# netCPU.net
KiCad netlist of a schematic drawn in EAGLE
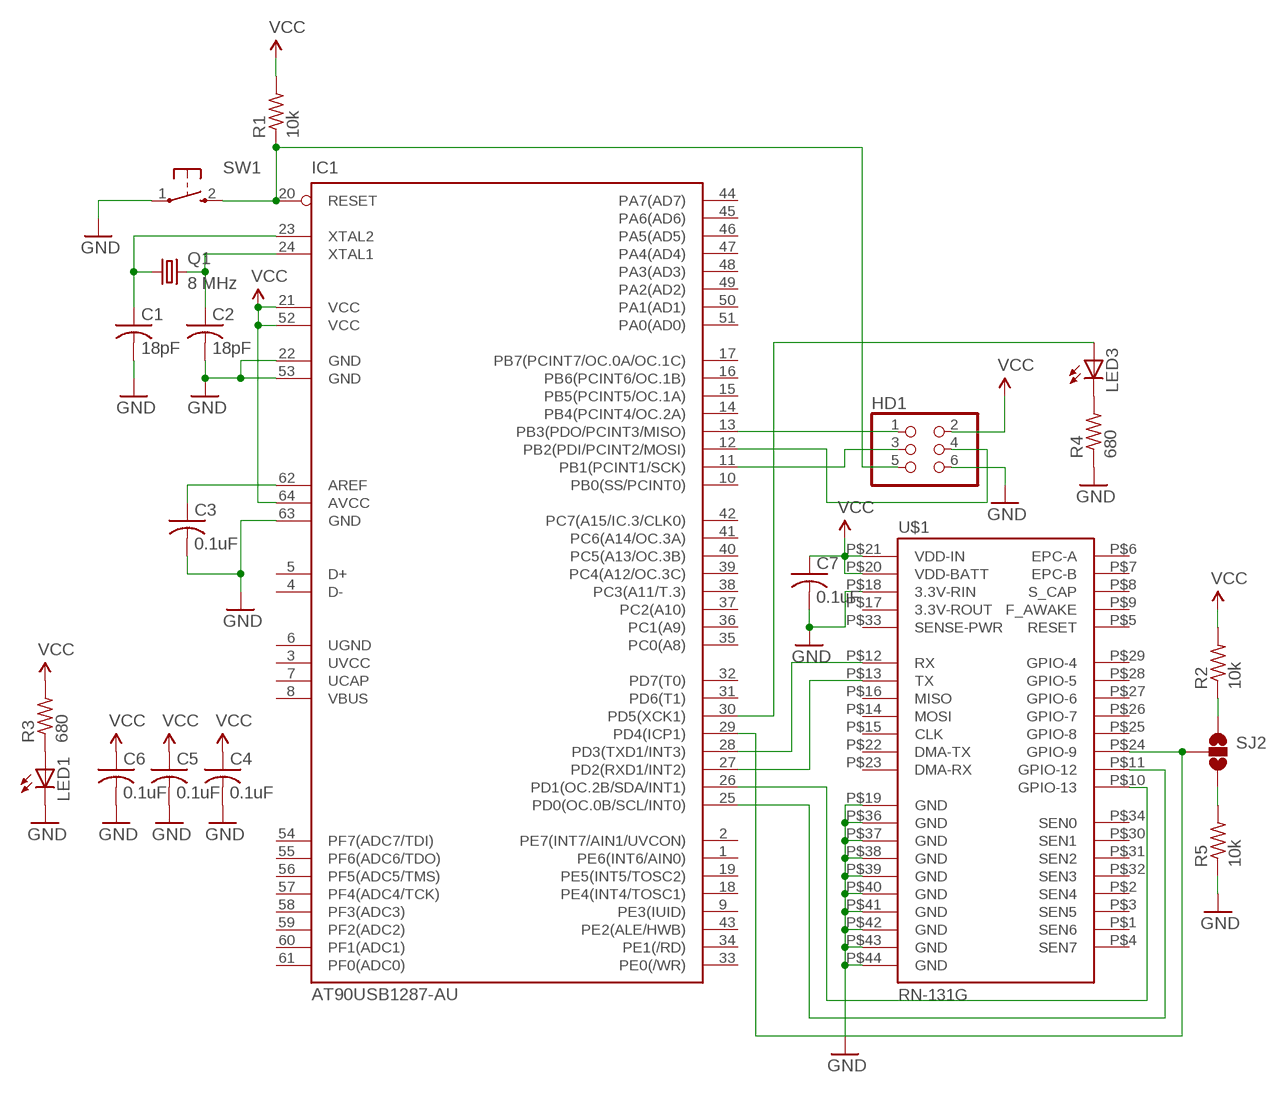
[diagram p0: schematic, sheet 1]

(export (version "E")
  (design (tool "Eeschema 10.0.6"))
  (components
    (comp (ref "C1")
      (value "18pF")
      (footprint "eagle-import:C0603K")
      (libsource (lib "eagle-import") (part "C-USC0603K"))
    )
    (comp (ref "C2")
      (value "18pF")
      (footprint "eagle-import:C0603K")
      (libsource (lib "eagle-import") (part "C-USC0603K"))
    )
    (comp (ref "C3")
      (value "0.1uF")
      (footprint "eagle-import:C0603K")
      (libsource (lib "eagle-import") (part "C-USC0603K"))
    )
    (comp (ref "C4")
      (value "0.1uF")
      (footprint "eagle-import:C0603K")
      (libsource (lib "eagle-import") (part "C-USC0603K"))
    )
    (comp (ref "C5")
      (value "0.1uF")
      (footprint "eagle-import:C0603K")
      (libsource (lib "eagle-import") (part "C-USC0603K"))
    )
    (comp (ref "C6")
      (value "0.1uF")
      (footprint "eagle-import:C0603K")
      (libsource (lib "eagle-import") (part "C-USC0603K"))
    )
    (comp (ref "C7")
      (value "0.1uF")
      (footprint "eagle-import:C0603K")
      (libsource (lib "eagle-import") (part "C-USC0603K"))
    )
    (comp (ref "HD1")
      (value "HEADER2X3")
      (footprint "eagle-import:HEADER2X3")
      (libsource (lib "eagle-import") (part "HEADER2X3"))
    )
    (comp (ref "IC1")
      (value "AT90USB1287-AU")
      (footprint "eagle-import:TQFP64")
      (libsource (lib "eagle-import") (part "AT90USB1287-AU"))
    )
    (comp (ref "LED1")
      (value "LEDCHIP-LED0603")
      (footprint "eagle-import:CHIP-LED0603")
      (libsource (lib "eagle-import") (part "LEDCHIP-LED0603"))
    )
    (comp (ref "LED3")
      (value "LEDCHIP-LED0603")
      (footprint "eagle-import:CHIP-LED0603")
      (libsource (lib "eagle-import") (part "LEDCHIP-LED0603"))
    )
    (comp (ref "Q1")
      (value "8 MHz")
      (footprint "eagle-import:HC49UP")
      (libsource (lib "eagle-import") (part "CRYSTALHC49UP"))
    )
    (comp (ref "R1")
      (value "10k")
      (footprint "eagle-import:R0603")
      (libsource (lib "eagle-import") (part "R-US_R0603"))
    )
    (comp (ref "R2")
      (value "10k")
      (footprint "eagle-import:R0603")
      (libsource (lib "eagle-import") (part "R-US_R0603"))
    )
    (comp (ref "R3")
      (value "680")
      (footprint "eagle-import:R0603")
      (libsource (lib "eagle-import") (part "R-US_R0603"))
    )
    (comp (ref "R4")
      (value "680")
      (footprint "eagle-import:R0603")
      (libsource (lib "eagle-import") (part "R-US_R0603"))
    )
    (comp (ref "R5")
      (value "10k")
      (footprint "eagle-import:R0603")
      (libsource (lib "eagle-import") (part "R-US_R0603"))
    )
    (comp (ref "SJ2")
      (value "SOLDERJUMPER_2WAYPASTE2&3")
      (footprint "eagle-import:SJ_3_PASTE2&3")
      (libsource (lib "eagle-import") (part "SOLDERJUMPER_2WAYPASTE2&3"))
    )
    (comp (ref "SW1")
      (value "TAC-SWITCH")
      (footprint "eagle-import:TAC-SWITCH")
      (libsource (lib "eagle-import") (part "TAC-SWITCH"))
    )
    (comp (ref "U$1")
      (value "RN-131G")
      (footprint "eagle-import:RN-131G")
      (libsource (lib "eagle-import") (part "RN-131G"))
    )
  )
  (nets
    (net (code "1") (name "/UCAP") (class "Default")
      (node (ref "IC1") (pin "7") (pinfunction "UCAP_7") (pintype "power_in"))
    )
    (net (code "2") (name "/UGND") (class "Default")
      (node (ref "IC1") (pin "6") (pinfunction "UGND_6") (pintype "power_in"))
    )
    (net (code "3") (name "/UVCC") (class "Default")
      (node (ref "IC1") (pin "3") (pinfunction "UVCC_3") (pintype "power_in"))
    )
    (net (code "4") (name "/VBUS") (class "Default")
      (node (ref "IC1") (pin "8") (pinfunction "VBUS_8") (pintype "power_in"))
    )
    (net (code "5") (name "GND") (class "Default")
      (node (ref "C1") (pin "2") (pinfunction "2_2") (pintype "passive"))
      (node (ref "C2") (pin "2") (pinfunction "2_2") (pintype "passive"))
      (node (ref "C3") (pin "2") (pinfunction "2_2") (pintype "passive"))
      (node (ref "C4") (pin "2") (pinfunction "2_2") (pintype "passive"))
      (node (ref "C5") (pin "2") (pinfunction "2_2") (pintype "passive"))
      (node (ref "C6") (pin "2") (pinfunction "2_2") (pintype "passive"))
      (node (ref "C7") (pin "2") (pinfunction "2_2") (pintype "passive"))
      (node (ref "HD1") (pin "6") (pinfunction "6_6") (pintype "passive"))
      (node (ref "IC1") (pin "22") (pinfunction "GND_22") (pintype "power_in"))
      (node (ref "IC1") (pin "53") (pinfunction "GND_53") (pintype "power_in"))
      (node (ref "IC1") (pin "63") (pinfunction "GND_63") (pintype "power_in"))
      (node (ref "LED1") (pin "C") (pinfunction "C_C") (pintype "passive"))
      (node (ref "R4") (pin "1") (pinfunction "1_1") (pintype "passive"))
      (node (ref "R5") (pin "1") (pinfunction "1_1") (pintype "passive"))
      (node (ref "SW1") (pin "1") (pinfunction "1_1") (pintype "passive"))
      (node (ref "U$1") (pin "P$18") (pinfunction "3.3V-RIN_P$18") (pintype "bidirectional"))
      (node (ref "U$1") (pin "P$19") (pinfunction "GND_P$19") (pintype "bidirectional"))
      (node (ref "U$1") (pin "P$36") (pinfunction "GND_P$36") (pintype "bidirectional"))
      (node (ref "U$1") (pin "P$37") (pinfunction "GND_P$37") (pintype "bidirectional"))
      (node (ref "U$1") (pin "P$38") (pinfunction "GND_P$38") (pintype "bidirectional"))
      (node (ref "U$1") (pin "P$39") (pinfunction "GND_P$39") (pintype "bidirectional"))
      (node (ref "U$1") (pin "P$40") (pinfunction "GND_P$40") (pintype "bidirectional"))
      (node (ref "U$1") (pin "P$41") (pinfunction "GND_P$41") (pintype "bidirectional"))
      (node (ref "U$1") (pin "P$42") (pinfunction "GND_P$42") (pintype "bidirectional"))
      (node (ref "U$1") (pin "P$43") (pinfunction "GND_P$43") (pintype "bidirectional"))
      (node (ref "U$1") (pin "P$44") (pinfunction "GND_P$44") (pintype "bidirectional"))
    )
    (net (code "6") (name "Net-(IC1-AREF)") (class "Default")
      (node (ref "C3") (pin "1") (pinfunction "1_1") (pintype "passive"))
      (node (ref "IC1") (pin "62") (pinfunction "AREF_62") (pintype "bidirectional"))
    )
    (net (code "7") (name "Net-(IC1-PB1(PCINT1{slash}SCK))") (class "Default")
      (node (ref "HD1") (pin "3") (pinfunction "3_3") (pintype "passive"))
      (node (ref "IC1") (pin "11") (pinfunction "PB1(PCINT1/SCK)_11") (pintype "bidirectional"))
    )
    (net (code "8") (name "Net-(IC1-PB2(PDI{slash}PCINT2{slash}MOSI))") (class "Default")
      (node (ref "HD1") (pin "4") (pinfunction "4_4") (pintype "passive"))
      (node (ref "IC1") (pin "12") (pinfunction "PB2(PDI/PCINT2/MOSI)_12") (pintype "bidirectional"))
    )
    (net (code "9") (name "Net-(IC1-PB3(PDO{slash}PCINT3{slash}MISO))") (class "Default")
      (node (ref "HD1") (pin "1") (pinfunction "1_1") (pintype "passive"))
      (node (ref "IC1") (pin "13") (pinfunction "PB3(PDO/PCINT3/MISO)_13") (pintype "bidirectional"))
    )
    (net (code "10") (name "Net-(IC1-PD0(OC.0B{slash}SCL{slash}INT0))") (class "Default")
      (node (ref "IC1") (pin "25") (pinfunction "PD0(OC.0B/SCL/INT0)_25") (pintype "bidirectional"))
      (node (ref "U$1") (pin "P$11") (pinfunction "GPIO-12_P$11") (pintype "bidirectional"))
    )
    (net (code "11") (name "Net-(IC1-PD1(OC.2B{slash}SDA{slash}INT1))") (class "Default")
      (node (ref "IC1") (pin "26") (pinfunction "PD1(OC.2B/SDA/INT1)_26") (pintype "bidirectional"))
      (node (ref "U$1") (pin "P$10") (pinfunction "GPIO-13_P$10") (pintype "bidirectional"))
    )
    (net (code "12") (name "Net-(IC1-PD2(RXD1{slash}INT2))") (class "Default")
      (node (ref "IC1") (pin "27") (pinfunction "PD2(RXD1/INT2)_27") (pintype "bidirectional"))
      (node (ref "U$1") (pin "P$13") (pinfunction "TX_P$13") (pintype "bidirectional"))
    )
    (net (code "13") (name "Net-(IC1-PD3(TXD1{slash}INT3))") (class "Default")
      (node (ref "IC1") (pin "28") (pinfunction "PD3(TXD1/INT3)_28") (pintype "bidirectional"))
      (node (ref "U$1") (pin "P$12") (pinfunction "RX_P$12") (pintype "bidirectional"))
    )
    (net (code "14") (name "Net-(IC1-PD4(ICP1))") (class "Default")
      (node (ref "IC1") (pin "29") (pinfunction "PD4(ICP1)_29") (pintype "bidirectional"))
      (node (ref "SJ2") (pin "2") (pinfunction "2_2") (pintype "passive"))
      (node (ref "U$1") (pin "P$24") (pinfunction "GPIO-9_P$24") (pintype "bidirectional"))
    )
    (net (code "15") (name "Net-(IC1-PD5(XCK1))") (class "Default")
      (node (ref "IC1") (pin "30") (pinfunction "PD5(XCK1)_30") (pintype "bidirectional"))
      (node (ref "LED3") (pin "A") (pinfunction "A_A") (pintype "passive"))
    )
    (net (code "16") (name "Net-(IC1-RESET)") (class "Default")
      (node (ref "HD1") (pin "5") (pinfunction "5_5") (pintype "passive"))
      (node (ref "IC1") (pin "20") (pinfunction "RESET_20") (pintype "input"))
      (node (ref "R1") (pin "1") (pinfunction "1_1") (pintype "passive"))
      (node (ref "SW1") (pin "2") (pinfunction "2_2") (pintype "passive"))
    )
    (net (code "17") (name "Net-(IC1-XTAL1)") (class "Default")
      (node (ref "C2") (pin "1") (pinfunction "1_1") (pintype "passive"))
      (node (ref "IC1") (pin "24") (pinfunction "XTAL1_24") (pintype "bidirectional"))
      (node (ref "Q1") (pin "2") (pinfunction "2_2") (pintype "passive"))
    )
    (net (code "18") (name "Net-(IC1-XTAL2)") (class "Default")
      (node (ref "C1") (pin "1") (pinfunction "1_1") (pintype "passive"))
      (node (ref "IC1") (pin "23") (pinfunction "XTAL2_23") (pintype "bidirectional"))
      (node (ref "Q1") (pin "1") (pinfunction "1_1") (pintype "passive"))
    )
    (net (code "19") (name "Net-(LED1-PadA)") (class "Default")
      (node (ref "LED1") (pin "A") (pinfunction "A_A") (pintype "passive"))
      (node (ref "R3") (pin "1") (pinfunction "1_1") (pintype "passive"))
    )
    (net (code "20") (name "Net-(LED3-PadC)") (class "Default")
      (node (ref "LED3") (pin "C") (pinfunction "C_C") (pintype "passive"))
      (node (ref "R4") (pin "2") (pinfunction "2_2") (pintype "passive"))
    )
    (net (code "21") (name "Net-(R2-Pad1)") (class "Default")
      (node (ref "R2") (pin "1") (pinfunction "1_1") (pintype "passive"))
      (node (ref "SJ2") (pin "1") (pinfunction "1_1") (pintype "passive"))
    )
    (net (code "22") (name "Net-(R5-Pad2)") (class "Default")
      (node (ref "R5") (pin "2") (pinfunction "2_2") (pintype "passive"))
      (node (ref "SJ2") (pin "3") (pinfunction "3_3") (pintype "passive"))
    )
    (net (code "23") (name "VCC") (class "Default")
      (node (ref "C4") (pin "1") (pinfunction "1_1") (pintype "passive"))
      (node (ref "C5") (pin "1") (pinfunction "1_1") (pintype "passive"))
      (node (ref "C6") (pin "1") (pinfunction "1_1") (pintype "passive"))
      (node (ref "C7") (pin "1") (pinfunction "1_1") (pintype "passive"))
      (node (ref "HD1") (pin "2") (pinfunction "2_2") (pintype "passive"))
      (node (ref "IC1") (pin "21") (pinfunction "VCC_21") (pintype "power_in"))
      (node (ref "IC1") (pin "52") (pinfunction "VCC_52") (pintype "power_in"))
      (node (ref "IC1") (pin "64") (pinfunction "AVCC_64") (pintype "bidirectional"))
      (node (ref "R1") (pin "2") (pinfunction "2_2") (pintype "passive"))
      (node (ref "R2") (pin "2") (pinfunction "2_2") (pintype "passive"))
      (node (ref "R3") (pin "2") (pinfunction "2_2") (pintype "passive"))
      (node (ref "U$1") (pin "P$20") (pinfunction "VDD-BATT_P$20") (pintype "bidirectional"))
      (node (ref "U$1") (pin "P$21") (pinfunction "VDD-IN_P$21") (pintype "bidirectional"))
    )
    (net (code "24") (name "unconnected-(IC1-D+-Pad5)") (class "Default")
      (node (ref "IC1") (pin "5") (pinfunction "D+_5") (pintype "bidirectional"))
    )
    (net (code "25") (name "unconnected-(IC1-D--Pad4)") (class "Default")
      (node (ref "IC1") (pin "4") (pinfunction "D-_4") (pintype "bidirectional"))
    )
    (net (code "26") (name "unconnected-(IC1-PA0(AD0)-Pad51)") (class "Default")
      (node (ref "IC1") (pin "51") (pinfunction "PA0(AD0)_51") (pintype "bidirectional"))
    )
    (net (code "27") (name "unconnected-(IC1-PA1(AD1)-Pad50)") (class "Default")
      (node (ref "IC1") (pin "50") (pinfunction "PA1(AD1)_50") (pintype "bidirectional"))
    )
    (net (code "28") (name "unconnected-(IC1-PA2(AD2)-Pad49)") (class "Default")
      (node (ref "IC1") (pin "49") (pinfunction "PA2(AD2)_49") (pintype "bidirectional"))
    )
    (net (code "29") (name "unconnected-(IC1-PA3(AD3)-Pad48)") (class "Default")
      (node (ref "IC1") (pin "48") (pinfunction "PA3(AD3)_48") (pintype "bidirectional"))
    )
    (net (code "30") (name "unconnected-(IC1-PA4(AD4)-Pad47)") (class "Default")
      (node (ref "IC1") (pin "47") (pinfunction "PA4(AD4)_47") (pintype "bidirectional"))
    )
    (net (code "31") (name "unconnected-(IC1-PA5(AD5)-Pad46)") (class "Default")
      (node (ref "IC1") (pin "46") (pinfunction "PA5(AD5)_46") (pintype "bidirectional"))
    )
    (net (code "32") (name "unconnected-(IC1-PA6(AD6)-Pad45)") (class "Default")
      (node (ref "IC1") (pin "45") (pinfunction "PA6(AD6)_45") (pintype "bidirectional"))
    )
    (net (code "33") (name "unconnected-(IC1-PA7(AD7)-Pad44)") (class "Default")
      (node (ref "IC1") (pin "44") (pinfunction "PA7(AD7)_44") (pintype "bidirectional"))
    )
    (net (code "34") (name "unconnected-(IC1-PB0(SS{slash}PCINT0)-Pad10)") (class "Default")
      (node (ref "IC1") (pin "10") (pinfunction "PB0(SS/PCINT0)_10") (pintype "bidirectional"))
    )
    (net (code "35") (name "unconnected-(IC1-PB4(PCINT4{slash}OC.2A)-Pad14)") (class "Default")
      (node (ref "IC1") (pin "14") (pinfunction "PB4(PCINT4/OC.2A)_14") (pintype "bidirectional"))
    )
    (net (code "36") (name "unconnected-(IC1-PB5(PCINT5{slash}OC.1A)-Pad15)") (class "Default")
      (node (ref "IC1") (pin "15") (pinfunction "PB5(PCINT5/OC.1A)_15") (pintype "bidirectional"))
    )
    (net (code "37") (name "unconnected-(IC1-PB6(PCINT6{slash}OC.1B)-Pad16)") (class "Default")
      (node (ref "IC1") (pin "16") (pinfunction "PB6(PCINT6/OC.1B)_16") (pintype "bidirectional"))
    )
    (net (code "38") (name "unconnected-(IC1-PB7(PCINT7{slash}OC.0A{slash}OC.1C)-Pad17)") (class "Default")
      (node (ref "IC1") (pin "17") (pinfunction "PB7(PCINT7/OC.0A/OC.1C)_17") (pintype "bidirectional"))
    )
    (net (code "39") (name "unconnected-(IC1-PC0(A8)-Pad35)") (class "Default")
      (node (ref "IC1") (pin "35") (pinfunction "PC0(A8)_35") (pintype "bidirectional"))
    )
    (net (code "40") (name "unconnected-(IC1-PC1(A9)-Pad36)") (class "Default")
      (node (ref "IC1") (pin "36") (pinfunction "PC1(A9)_36") (pintype "bidirectional"))
    )
    (net (code "41") (name "unconnected-(IC1-PC2(A10)-Pad37)") (class "Default")
      (node (ref "IC1") (pin "37") (pinfunction "PC2(A10)_37") (pintype "bidirectional"))
    )
    (net (code "42") (name "unconnected-(IC1-PC3(A11{slash}T.3)-Pad38)") (class "Default")
      (node (ref "IC1") (pin "38") (pinfunction "PC3(A11/T.3)_38") (pintype "bidirectional"))
    )
    (net (code "43") (name "unconnected-(IC1-PC4(A12{slash}OC.3C)-Pad39)") (class "Default")
      (node (ref "IC1") (pin "39") (pinfunction "PC4(A12/OC.3C)_39") (pintype "bidirectional"))
    )
    (net (code "44") (name "unconnected-(IC1-PC5(A13{slash}OC.3B)-Pad40)") (class "Default")
      (node (ref "IC1") (pin "40") (pinfunction "PC5(A13/OC.3B)_40") (pintype "bidirectional"))
    )
    (net (code "45") (name "unconnected-(IC1-PC6(A14{slash}OC.3A)-Pad41)") (class "Default")
      (node (ref "IC1") (pin "41") (pinfunction "PC6(A14/OC.3A)_41") (pintype "bidirectional"))
    )
    (net (code "46") (name "unconnected-(IC1-PC7(A15{slash}IC.3{slash}CLK0)-Pad42)") (class "Default")
      (node (ref "IC1") (pin "42") (pinfunction "PC7(A15/IC.3/CLK0)_42") (pintype "bidirectional"))
    )
    (net (code "47") (name "unconnected-(IC1-PD6(T1)-Pad31)") (class "Default")
      (node (ref "IC1") (pin "31") (pinfunction "PD6(T1)_31") (pintype "bidirectional"))
    )
    (net (code "48") (name "unconnected-(IC1-PD7(T0)-Pad32)") (class "Default")
      (node (ref "IC1") (pin "32") (pinfunction "PD7(T0)_32") (pintype "bidirectional"))
    )
    (net (code "49") (name "unconnected-(IC1-PE0({slash}WR)-Pad33)") (class "Default")
      (node (ref "IC1") (pin "33") (pinfunction "PE0(/WR)_33") (pintype "bidirectional"))
    )
    (net (code "50") (name "unconnected-(IC1-PE1({slash}RD)-Pad34)") (class "Default")
      (node (ref "IC1") (pin "34") (pinfunction "PE1(/RD)_34") (pintype "bidirectional"))
    )
    (net (code "51") (name "unconnected-(IC1-PE2(ALE{slash}HWB)-Pad43)") (class "Default")
      (node (ref "IC1") (pin "43") (pinfunction "PE2(ALE/HWB)_43") (pintype "bidirectional"))
    )
    (net (code "52") (name "unconnected-(IC1-PE3(IUID)-Pad9)") (class "Default")
      (node (ref "IC1") (pin "9") (pinfunction "PE3(IUID)_9") (pintype "bidirectional"))
    )
    (net (code "53") (name "unconnected-(IC1-PE4(INT4{slash}TOSC1)-Pad18)") (class "Default")
      (node (ref "IC1") (pin "18") (pinfunction "PE4(INT4/TOSC1)_18") (pintype "bidirectional"))
    )
    (net (code "54") (name "unconnected-(IC1-PE5(INT5{slash}TOSC2)-Pad19)") (class "Default")
      (node (ref "IC1") (pin "19") (pinfunction "PE5(INT5/TOSC2)_19") (pintype "bidirectional"))
    )
    (net (code "55") (name "unconnected-(IC1-PE6(INT6{slash}AIN0)-Pad1)") (class "Default")
      (node (ref "IC1") (pin "1") (pinfunction "PE6(INT6/AIN0)_1") (pintype "bidirectional"))
    )
    (net (code "56") (name "unconnected-(IC1-PE7(INT7{slash}AIN1{slash}UVCON)-Pad2)") (class "Default")
      (node (ref "IC1") (pin "2") (pinfunction "PE7(INT7/AIN1/UVCON)_2") (pintype "bidirectional"))
    )
    (net (code "57") (name "unconnected-(IC1-PF0(ADC0)-Pad61)") (class "Default")
      (node (ref "IC1") (pin "61") (pinfunction "PF0(ADC0)_61") (pintype "bidirectional"))
    )
    (net (code "58") (name "unconnected-(IC1-PF1(ADC1)-Pad60)") (class "Default")
      (node (ref "IC1") (pin "60") (pinfunction "PF1(ADC1)_60") (pintype "bidirectional"))
    )
    (net (code "59") (name "unconnected-(IC1-PF2(ADC2)-Pad59)") (class "Default")
      (node (ref "IC1") (pin "59") (pinfunction "PF2(ADC2)_59") (pintype "bidirectional"))
    )
    (net (code "60") (name "unconnected-(IC1-PF3(ADC3)-Pad58)") (class "Default")
      (node (ref "IC1") (pin "58") (pinfunction "PF3(ADC3)_58") (pintype "bidirectional"))
    )
    (net (code "61") (name "unconnected-(IC1-PF4(ADC4{slash}TCK)-Pad57)") (class "Default")
      (node (ref "IC1") (pin "57") (pinfunction "PF4(ADC4/TCK)_57") (pintype "bidirectional"))
    )
    (net (code "62") (name "unconnected-(IC1-PF5(ADC5{slash}TMS)-Pad56)") (class "Default")
      (node (ref "IC1") (pin "56") (pinfunction "PF5(ADC5/TMS)_56") (pintype "bidirectional"))
    )
    (net (code "63") (name "unconnected-(IC1-PF6(ADC6{slash}TDO)-Pad55)") (class "Default")
      (node (ref "IC1") (pin "55") (pinfunction "PF6(ADC6/TDO)_55") (pintype "bidirectional"))
    )
    (net (code "64") (name "unconnected-(IC1-PF7(ADC7{slash}TDI)-Pad54)") (class "Default")
      (node (ref "IC1") (pin "54") (pinfunction "PF7(ADC7/TDI)_54") (pintype "bidirectional"))
    )
    (net (code "65") (name "unconnected-(U$1-3.3V-ROUT-PadP$17)") (class "Default")
      (node (ref "U$1") (pin "P$17") (pinfunction "3.3V-ROUT_P$17") (pintype "bidirectional"))
    )
    (net (code "66") (name "unconnected-(U$1-CLK-PadP$15)") (class "Default")
      (node (ref "U$1") (pin "P$15") (pinfunction "CLK_P$15") (pintype "bidirectional"))
    )
    (net (code "67") (name "unconnected-(U$1-DMA-RX-PadP$23)") (class "Default")
      (node (ref "U$1") (pin "P$23") (pinfunction "DMA-RX_P$23") (pintype "bidirectional"))
    )
    (net (code "68") (name "unconnected-(U$1-DMA-TX-PadP$22)") (class "Default")
      (node (ref "U$1") (pin "P$22") (pinfunction "DMA-TX_P$22") (pintype "bidirectional"))
    )
    (net (code "69") (name "unconnected-(U$1-EPC-A-PadP$6)") (class "Default")
      (node (ref "U$1") (pin "P$6") (pinfunction "EPC-A_P$6") (pintype "bidirectional"))
    )
    (net (code "70") (name "unconnected-(U$1-EPC-B-PadP$7)") (class "Default")
      (node (ref "U$1") (pin "P$7") (pinfunction "EPC-B_P$7") (pintype "bidirectional"))
    )
    (net (code "71") (name "unconnected-(U$1-F_AWAKE-PadP$9)") (class "Default")
      (node (ref "U$1") (pin "P$9") (pinfunction "F_AWAKE_P$9") (pintype "bidirectional"))
    )
    (net (code "72") (name "unconnected-(U$1-GPIO-4-PadP$29)") (class "Default")
      (node (ref "U$1") (pin "P$29") (pinfunction "GPIO-4_P$29") (pintype "bidirectional"))
    )
    (net (code "73") (name "unconnected-(U$1-GPIO-5-PadP$28)") (class "Default")
      (node (ref "U$1") (pin "P$28") (pinfunction "GPIO-5_P$28") (pintype "bidirectional"))
    )
    (net (code "74") (name "unconnected-(U$1-GPIO-6-PadP$27)") (class "Default")
      (node (ref "U$1") (pin "P$27") (pinfunction "GPIO-6_P$27") (pintype "bidirectional"))
    )
    (net (code "75") (name "unconnected-(U$1-GPIO-7-PadP$26)") (class "Default")
      (node (ref "U$1") (pin "P$26") (pinfunction "GPIO-7_P$26") (pintype "bidirectional"))
    )
    (net (code "76") (name "unconnected-(U$1-GPIO-8-PadP$25)") (class "Default")
      (node (ref "U$1") (pin "P$25") (pinfunction "GPIO-8_P$25") (pintype "bidirectional"))
    )
    (net (code "77") (name "unconnected-(U$1-MISO-PadP$16)") (class "Default")
      (node (ref "U$1") (pin "P$16") (pinfunction "MISO_P$16") (pintype "bidirectional"))
    )
    (net (code "78") (name "unconnected-(U$1-MOSI-PadP$14)") (class "Default")
      (node (ref "U$1") (pin "P$14") (pinfunction "MOSI_P$14") (pintype "bidirectional"))
    )
    (net (code "79") (name "unconnected-(U$1-RESET-PadP$5)") (class "Default")
      (node (ref "U$1") (pin "P$5") (pinfunction "RESET_P$5") (pintype "bidirectional"))
    )
    (net (code "80") (name "unconnected-(U$1-SEN0-PadP$34)") (class "Default")
      (node (ref "U$1") (pin "P$34") (pinfunction "SEN0_P$34") (pintype "bidirectional"))
    )
    (net (code "81") (name "unconnected-(U$1-SEN1-PadP$30)") (class "Default")
      (node (ref "U$1") (pin "P$30") (pinfunction "SEN1_P$30") (pintype "bidirectional"))
    )
    (net (code "82") (name "unconnected-(U$1-SEN2-PadP$31)") (class "Default")
      (node (ref "U$1") (pin "P$31") (pinfunction "SEN2_P$31") (pintype "bidirectional"))
    )
    (net (code "83") (name "unconnected-(U$1-SEN3-PadP$32)") (class "Default")
      (node (ref "U$1") (pin "P$32") (pinfunction "SEN3_P$32") (pintype "bidirectional"))
    )
    (net (code "84") (name "unconnected-(U$1-SEN4-PadP$2)") (class "Default")
      (node (ref "U$1") (pin "P$2") (pinfunction "SEN4_P$2") (pintype "bidirectional"))
    )
    (net (code "85") (name "unconnected-(U$1-SEN5-PadP$3)") (class "Default")
      (node (ref "U$1") (pin "P$3") (pinfunction "SEN5_P$3") (pintype "bidirectional"))
    )
    (net (code "86") (name "unconnected-(U$1-SEN6-PadP$1)") (class "Default")
      (node (ref "U$1") (pin "P$1") (pinfunction "SEN6_P$1") (pintype "bidirectional"))
    )
    (net (code "87") (name "unconnected-(U$1-SEN7-PadP$4)") (class "Default")
      (node (ref "U$1") (pin "P$4") (pinfunction "SEN7_P$4") (pintype "bidirectional"))
    )
    (net (code "88") (name "unconnected-(U$1-SENSE-PWR-PadP$33)") (class "Default")
      (node (ref "U$1") (pin "P$33") (pinfunction "SENSE-PWR_P$33") (pintype "bidirectional"))
    )
    (net (code "89") (name "unconnected-(U$1-S_CAP-PadP$8)") (class "Default")
      (node (ref "U$1") (pin "P$8") (pinfunction "S_CAP_P$8") (pintype "bidirectional"))
    )
  )
)
